# wifi_watering_system_1.net
KiCad netlist of a schematic drawn in Altium Designer
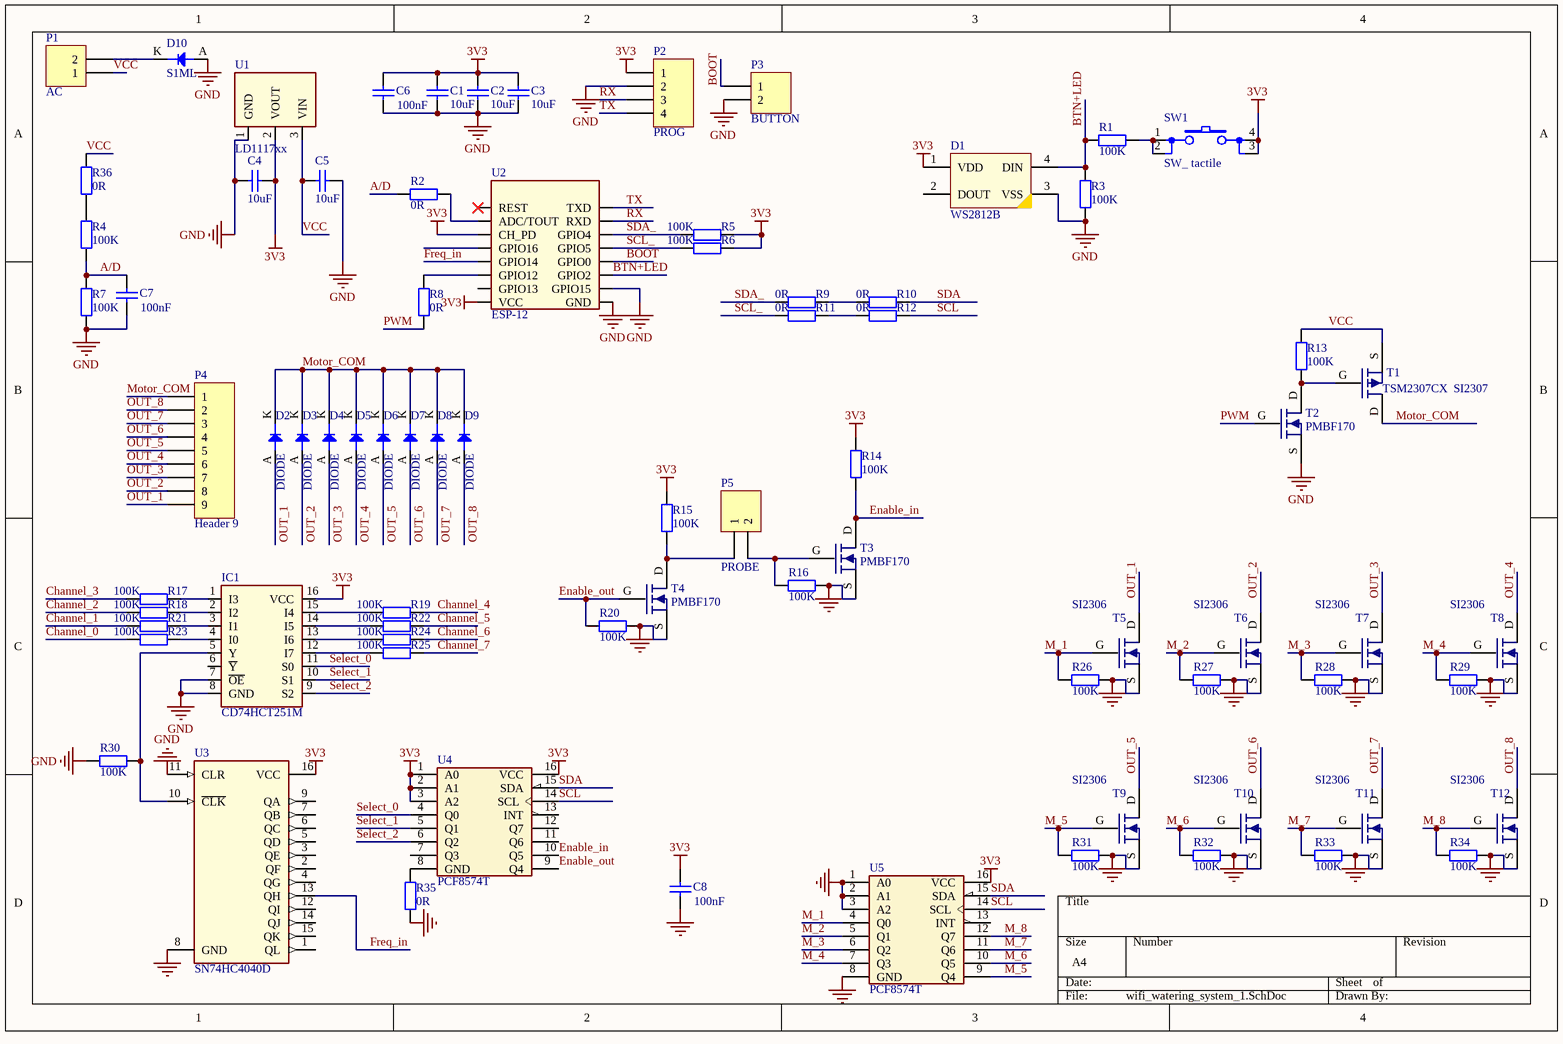
[diagram p0: wifi_watering_system_1.SchDoc]

(export (version "E")
  (design (tool "Eeschema 10.0.6"))
  (components
    (comp (ref "C1")
      (value "10uF")
      (footprint "FP_1206_CAP_085")
      (description "Capacitor")
      (fields (field (name "PUBLISHER") "Altium Limited"))
      (libsource (lib "Miscellaneous Devices") (part "Cap"))
    )
    (comp (ref "C2")
      (value "10uF")
      (footprint "FP_1206_CAP_085")
      (description "Capacitor")
      (fields (field (name "PUBLISHER") "Altium Limited"))
      (libsource (lib "Miscellaneous Devices") (part "Cap"))
    )
    (comp (ref "C3")
      (value "10uF")
      (footprint "FP_1206_CAP_085")
      (description "Capacitor")
      (fields (field (name "PUBLISHER") "Altium Limited"))
      (libsource (lib "Miscellaneous Devices") (part "Cap"))
    )
    (comp (ref "C4")
      (value "10uF")
      (footprint "FP_1206_CAP_085")
      (description "Capacitor")
      (fields (field (name "PUBLISHER") "Altium Limited"))
      (libsource (lib "Miscellaneous Devices") (part "Cap"))
    )
    (comp (ref "C5")
      (value "10uF")
      (footprint "FP_1206_CAP_085")
      (description "Capacitor")
      (fields (field (name "PUBLISHER") "Altium Limited"))
      (libsource (lib "Miscellaneous Devices") (part "Cap"))
    )
    (comp (ref "C6")
      (value "100nF")
      (footprint "FP_0603_CAP_080")
      (description "Capacitor")
      (libsource (lib "Miscellaneous Devices") (part "Cap"))
    )
    (comp (ref "C7")
      (value "100nF")
      (footprint "FP_0603_CAP_080")
      (description "Capacitor")
      (libsource (lib "Miscellaneous Devices") (part "Cap"))
    )
    (comp (ref "C8")
      (value "100nF")
      (footprint "FP_0603_CAP_080")
      (description "Capacitor")
      (libsource (lib "Miscellaneous Devices") (part "Cap"))
    )
    (comp (ref "D1")
      (value "WS2812B")
      (footprint "LED_5050_4pin")
      (libsource (lib "Led_optical") (part "WS2812B"))
    )
    (comp (ref "D2")
      (value "DIODE")
      (footprint "SOD-80")
      (description "Diode")
      (libsource (lib "Diode") (part "DIODE"))
    )
    (comp (ref "D3")
      (value "DIODE")
      (footprint "SOD-80")
      (description "Diode")
      (libsource (lib "Diode") (part "DIODE"))
    )
    (comp (ref "D4")
      (value "DIODE")
      (footprint "SOD-80")
      (description "Diode")
      (libsource (lib "Diode") (part "DIODE"))
    )
    (comp (ref "D5")
      (value "DIODE")
      (footprint "SOD-80")
      (description "Diode")
      (libsource (lib "Diode") (part "DIODE"))
    )
    (comp (ref "D6")
      (value "DIODE")
      (footprint "SOD-80")
      (description "Diode")
      (libsource (lib "Diode") (part "DIODE"))
    )
    (comp (ref "D7")
      (value "DIODE")
      (footprint "SOD-80")
      (description "Diode")
      (libsource (lib "Diode") (part "DIODE"))
    )
    (comp (ref "D8")
      (value "DIODE")
      (footprint "SOD-80")
      (description "Diode")
      (libsource (lib "Diode") (part "DIODE"))
    )
    (comp (ref "D9")
      (value "DIODE")
      (footprint "SOD-80")
      (description "Diode")
      (libsource (lib "Diode") (part "DIODE"))
    )
    (comp (ref "D10")
      (value "S1ML")
      (footprint "subsma")
      (description "Diode")
      (libsource (lib "Diode") (part "DIODE"))
    )
    (comp (ref "IC1")
      (value "CD74HCT251M")
      (footprint "GATE_SOIC16")
      (description "CD74HCT251M 8-INPUT MUX.WITH 3-STATE OUTP")
      (libsource (lib "Logic_gate") (part "CD74HCT251M"))
    )
    (comp (ref "P1")
      (value "AC")
      (footprint "Sorkapocs 2P 5mm")
      (description "Header, 2-Pin")
      (fields (field (name "PUBLISHER") "Altium Limited"))
      (libsource (lib "Miscellaneous Connectors") (part "Header 2"))
    )
    (comp (ref "P2")
      (value "PROG")
      (footprint "HDR1X4")
      (description "Header, 4-Pin")
      (fields (field (name "PUBLISHER") "Altium Limited"))
      (libsource (lib "Miscellaneous Connectors") (part "Header 4"))
    )
    (comp (ref "P3")
      (value "BUTTON")
      (footprint "HDR1X2")
      (description "Header, 2-Pin")
      (fields (field (name "PUBLISHER") "Altium Limited"))
      (libsource (lib "") (part "Header 2_1"))
    )
    (comp (ref "P4")
      (value "Header 9")
      (footprint "Sorkapocs 9P 5mm")
      (description "Header, 9-Pin")
      (fields (field (name "PUBLISHER") "Altium Limited"))
      (libsource (lib "Miscellaneous Connectors") (part "Header 9"))
    )
    (comp (ref "P5")
      (value "PROBE")
      (footprint "HDR1X2")
      (description "Header, 2-Pin")
      (fields (field (name "PUBLISHER") "Altium Limited"))
      (libsource (lib "") (part "Header 2_2"))
    )
    (comp (ref "R1")
      (value "100K")
      (footprint "FP_0603_RES")
      (description "Resistor")
      (libsource (lib "Resistor") (part "RES"))
    )
    (comp (ref "R2")
      (value "0R")
      (footprint "FP_1206_RES")
      (description "Resistor")
      (libsource (lib "") (part "RES_3"))
    )
    (comp (ref "R3")
      (value "100K")
      (footprint "FP_0603_RES")
      (description "Resistor")
      (libsource (lib "") (part "RES_2"))
    )
    (comp (ref "R4")
      (value "100K")
      (footprint "FP_0603_RES")
      (description "Resistor")
      (libsource (lib "") (part "RES_2"))
    )
    (comp (ref "R5")
      (value "100K")
      (footprint "FP_0603_RES")
      (description "Resistor")
      (libsource (lib "") (part "RES_3"))
    )
    (comp (ref "R6")
      (value "100K")
      (footprint "FP_0603_RES")
      (description "Resistor")
      (libsource (lib "") (part "RES_3"))
    )
    (comp (ref "R7")
      (value "100K")
      (footprint "FP_0603_RES")
      (description "Resistor")
      (libsource (lib "") (part "RES_2"))
    )
    (comp (ref "R8")
      (value "0R")
      (footprint "FP_1206_RES")
      (description "Resistor")
      (libsource (lib "") (part "RES_2"))
    )
    (comp (ref "R9")
      (value "0R")
      (footprint "FP_1206_RES")
      (description "Resistor")
      (libsource (lib "") (part "RES_3"))
    )
    (comp (ref "R10")
      (value "0R")
      (footprint "FP_1206_RES")
      (description "Resistor")
      (libsource (lib "") (part "RES_3"))
    )
    (comp (ref "R11")
      (value "0R")
      (footprint "FP_1206_RES")
      (description "Resistor")
      (libsource (lib "") (part "RES_3"))
    )
    (comp (ref "R12")
      (value "0R")
      (footprint "FP_1206_RES")
      (description "Resistor")
      (libsource (lib "") (part "RES_3"))
    )
    (comp (ref "R13")
      (value "100K")
      (footprint "FP_0603_RES")
      (description "Resistor")
      (libsource (lib "") (part "RES_2"))
    )
    (comp (ref "R14")
      (value "100K")
      (footprint "FP_0603_RES")
      (description "Resistor")
      (libsource (lib "") (part "RES_1"))
    )
    (comp (ref "R15")
      (value "100K")
      (footprint "FP_0603_RES")
      (description "Resistor")
      (libsource (lib "") (part "RES_1"))
    )
    (comp (ref "R16")
      (value "100K")
      (footprint "FP_0603_RES")
      (description "Resistor")
      (libsource (lib "") (part "RES_3"))
    )
    (comp (ref "R17")
      (value "100K")
      (footprint "FP_0603_RES")
      (description "Resistor")
      (libsource (lib "Resistor") (part "RES"))
    )
    (comp (ref "R18")
      (value "100K")
      (footprint "FP_0603_RES")
      (description "Resistor")
      (libsource (lib "Resistor") (part "RES"))
    )
    (comp (ref "R19")
      (value "100K")
      (footprint "FP_0603_RES")
      (description "Resistor")
      (libsource (lib "Resistor") (part "RES"))
    )
    (comp (ref "R20")
      (value "100K")
      (footprint "FP_0603_RES")
      (description "Resistor")
      (libsource (lib "") (part "RES_3"))
    )
    (comp (ref "R21")
      (value "100K")
      (footprint "FP_0603_RES")
      (description "Resistor")
      (libsource (lib "Resistor") (part "RES"))
    )
    (comp (ref "R22")
      (value "100K")
      (footprint "FP_0603_RES")
      (description "Resistor")
      (libsource (lib "Resistor") (part "RES"))
    )
    (comp (ref "R23")
      (value "100K")
      (footprint "FP_0603_RES")
      (description "Resistor")
      (libsource (lib "Resistor") (part "RES"))
    )
    (comp (ref "R24")
      (value "100K")
      (footprint "FP_0603_RES")
      (description "Resistor")
      (libsource (lib "Resistor") (part "RES"))
    )
    (comp (ref "R25")
      (value "100K")
      (footprint "FP_0603_RES")
      (description "Resistor")
      (libsource (lib "Resistor") (part "RES"))
    )
    (comp (ref "R26")
      (value "100K")
      (footprint "FP_0603_RES")
      (description "Resistor")
      (libsource (lib "Resistor") (part "RES"))
    )
    (comp (ref "R27")
      (value "100K")
      (footprint "FP_0603_RES")
      (description "Resistor")
      (libsource (lib "") (part "RES_3"))
    )
    (comp (ref "R28")
      (value "100K")
      (footprint "FP_0603_RES")
      (description "Resistor")
      (libsource (lib "") (part "RES_3"))
    )
    (comp (ref "R29")
      (value "100K")
      (footprint "FP_0603_RES")
      (description "Resistor")
      (libsource (lib "") (part "RES_3"))
    )
    (comp (ref "R30")
      (value "100K")
      (footprint "FP_0603_RES")
      (description "Resistor")
      (libsource (lib "Resistor") (part "RES"))
    )
    (comp (ref "R31")
      (value "100K")
      (footprint "FP_0603_RES")
      (description "Resistor")
      (libsource (lib "") (part "RES_3"))
    )
    (comp (ref "R32")
      (value "100K")
      (footprint "FP_0603_RES")
      (description "Resistor")
      (libsource (lib "") (part "RES_3"))
    )
    (comp (ref "R33")
      (value "100K")
      (footprint "FP_0603_RES")
      (description "Resistor")
      (libsource (lib "") (part "RES_3"))
    )
    (comp (ref "R34")
      (value "100K")
      (footprint "FP_0603_RES")
      (description "Resistor")
      (libsource (lib "") (part "RES_3"))
    )
    (comp (ref "R35")
      (value "0R")
      (footprint "FP_1206_RES")
      (description "Resistor")
      (libsource (lib "") (part "RES_2"))
    )
    (comp (ref "R36")
      (value "0R")
      (footprint "FP_1206_RES")
      (description "Resistor")
      (libsource (lib "") (part "RES_2"))
    )
    (comp (ref "SW1")
      (value "SW_ tactile")
      (footprint "FP_TACTBTN")
      (libsource (lib "Switch") (part "SW_ tactile"))
    )
    (comp (ref "T1")
      (value "TSM2307CX  SI2307")
      (footprint "FET_SOT23")
      (libsource (lib "FET") (part "PMOS"))
    )
    (comp (ref "T2") (value "PMBF170") (footprint "FET_SOT23") (libsource (lib "FET") (part "NMOS")))
    (comp (ref "T3") (value "PMBF170") (footprint "FET_SOT23") (libsource (lib "FET") (part "NMOS")))
    (comp (ref "T4") (value "PMBF170") (footprint "FET_SOT23") (libsource (lib "FET") (part "NMOS")))
    (comp (ref "T5") (value "SI2306") (footprint "FET_SOT23") (libsource (lib "FET") (part "NMOS")))
    (comp (ref "T6") (value "SI2306") (footprint "FET_SOT23") (libsource (lib "FET") (part "NMOS")))
    (comp (ref "T7") (value "SI2306") (footprint "FET_SOT23") (libsource (lib "FET") (part "NMOS")))
    (comp (ref "T8") (value "SI2306") (footprint "FET_SOT23") (libsource (lib "FET") (part "NMOS")))
    (comp (ref "T9") (value "SI2306") (footprint "FET_SOT23") (libsource (lib "FET") (part "NMOS")))
    (comp (ref "T10") (value "SI2306") (footprint "FET_SOT23") (libsource (lib "FET") (part "NMOS")))
    (comp (ref "T11") (value "SI2306") (footprint "FET_SOT23") (libsource (lib "FET") (part "NMOS")))
    (comp (ref "T12") (value "SI2306") (footprint "FET_SOT23") (libsource (lib "FET") (part "NMOS")))
    (comp (ref "U1")
      (value "LD1117xx")
      (footprint "SUPPLY_SOT223")
      (description "LD1117xx 3,3V lin reg")
      (libsource (lib "Supply") (part "LD1117xx"))
    )
    (comp (ref "U2")
      (value "ESP-12")
      (footprint "ESP_12")
      (description "ESP-12 wifi module")
      (libsource (lib "Modul") (part "ESP-12"))
    )
    (comp (ref "U3")
      (value "SN74HC4040D")
      (footprint "GATE_SOIC16")
      (description "12-Bit Asynchronous Binary Counter")
      (libsource (lib "Logic_gate") (part "SN74HC4040D"))
    )
    (comp (ref "U4")
      (value "PCF8574T")
      (footprint "DIGITAL_SOIC16W")
      (libsource (lib "Digital") (part "PCF8574T"))
    )
    (comp (ref "U5")
      (value "PCF8574T")
      (footprint "DIGITAL_SOIC16W")
      (libsource (lib "Digital") (part "PCF8574T"))
    )
  )
  (nets
    (net (code "1") (name "/A{slash}D") (class "Default")
      (node (ref "C7") (pin "1") (pinfunction "1_1") (pintype "passive"))
      (node (ref "R2") (pin "2") (pinfunction "2_2") (pintype "passive"))
      (node (ref "R4") (pin "2") (pinfunction "2_2") (pintype "passive"))
      (node (ref "R7") (pin "1") (pinfunction "1_1") (pintype "passive"))
    )
    (net (code "2") (name "/BOOT") (class "Default")
      (node (ref "P3") (pin "1") (pinfunction "1_1") (pintype "passive"))
      (node (ref "U2") (pin "12") (pinfunction "GPIO0_12") (pintype "passive"))
    )
    (net (code "3") (name "/BTN+LED") (class "Default")
      (node (ref "D1") (pin "4") (pinfunction "DIN_4") (pintype "passive"))
      (node (ref "R1") (pin "1") (pinfunction "1_1") (pintype "passive"))
      (node (ref "R3") (pin "1") (pinfunction "1_1") (pintype "passive"))
      (node (ref "U2") (pin "11") (pinfunction "GPIO2_11") (pintype "passive"))
    )
    (net (code "4") (name "/Channel_0") (class "Default")
      (node (ref "R23") (pin "1") (pinfunction "1_1") (pintype "passive"))
    )
    (net (code "5") (name "/Channel_1") (class "Default")
      (node (ref "R21") (pin "1") (pinfunction "1_1") (pintype "passive"))
    )
    (net (code "6") (name "/Channel_2") (class "Default")
      (node (ref "R18") (pin "1") (pinfunction "1_1") (pintype "passive"))
    )
    (net (code "7") (name "/Channel_3") (class "Default")
      (node (ref "R17") (pin "1") (pinfunction "1_1") (pintype "passive"))
    )
    (net (code "8") (name "/Channel_4") (class "Default")
      (node (ref "R19") (pin "2") (pinfunction "2_2") (pintype "passive"))
    )
    (net (code "9") (name "/Channel_5") (class "Default")
      (node (ref "R22") (pin "2") (pinfunction "2_2") (pintype "passive"))
    )
    (net (code "10") (name "/Channel_6") (class "Default")
      (node (ref "R24") (pin "2") (pinfunction "2_2") (pintype "passive"))
    )
    (net (code "11") (name "/Channel_7") (class "Default")
      (node (ref "R25") (pin "2") (pinfunction "2_2") (pintype "passive"))
    )
    (net (code "12") (name "/Enable_in") (class "Default")
      (node (ref "R14") (pin "1") (pinfunction "1_1") (pintype "passive"))
      (node (ref "T3") (pin "D") (pinfunction "D_D") (pintype "passive"))
      (node (ref "U4") (pin "10") (pinfunction "Q5_10") (pintype "passive"))
    )
    (net (code "13") (name "/Enable_out") (class "Default")
      (node (ref "R20") (pin "2") (pinfunction "2_2") (pintype "passive"))
      (node (ref "T4") (pin "G") (pinfunction "G_G") (pintype "passive"))
      (node (ref "U4") (pin "9") (pinfunction "Q4_9") (pintype "passive"))
    )
    (net (code "14") (name "/Freq_in") (class "Default")
      (node (ref "U2") (pin "5") (pinfunction "GPIO14_5") (pintype "passive"))
      (node (ref "U3") (pin "13") (pinfunction "QH_13") (pintype "output"))
    )
    (net (code "15") (name "/M_1") (class "Default")
      (node (ref "R26") (pin "1") (pinfunction "1_1") (pintype "passive"))
      (node (ref "T5") (pin "G") (pinfunction "G_G") (pintype "passive"))
      (node (ref "U5") (pin "4") (pinfunction "Q0_4") (pintype "passive"))
    )
    (net (code "16") (name "/M_2") (class "Default")
      (node (ref "R27") (pin "2") (pinfunction "2_2") (pintype "passive"))
      (node (ref "T6") (pin "G") (pinfunction "G_G") (pintype "passive"))
      (node (ref "U5") (pin "5") (pinfunction "Q1_5") (pintype "passive"))
    )
    (net (code "17") (name "/M_3") (class "Default")
      (node (ref "R28") (pin "2") (pinfunction "2_2") (pintype "passive"))
      (node (ref "T7") (pin "G") (pinfunction "G_G") (pintype "passive"))
      (node (ref "U5") (pin "6") (pinfunction "Q2_6") (pintype "passive"))
    )
    (net (code "18") (name "/M_4") (class "Default")
      (node (ref "R29") (pin "2") (pinfunction "2_2") (pintype "passive"))
      (node (ref "T8") (pin "G") (pinfunction "G_G") (pintype "passive"))
      (node (ref "U5") (pin "7") (pinfunction "Q3_7") (pintype "passive"))
    )
    (net (code "19") (name "/M_5") (class "Default")
      (node (ref "R31") (pin "2") (pinfunction "2_2") (pintype "passive"))
      (node (ref "T9") (pin "G") (pinfunction "G_G") (pintype "passive"))
      (node (ref "U5") (pin "9") (pinfunction "Q4_9") (pintype "passive"))
    )
    (net (code "20") (name "/M_6") (class "Default")
      (node (ref "R32") (pin "2") (pinfunction "2_2") (pintype "passive"))
      (node (ref "T10") (pin "G") (pinfunction "G_G") (pintype "passive"))
      (node (ref "U5") (pin "10") (pinfunction "Q5_10") (pintype "passive"))
    )
    (net (code "21") (name "/M_7") (class "Default")
      (node (ref "R33") (pin "2") (pinfunction "2_2") (pintype "passive"))
      (node (ref "T11") (pin "G") (pinfunction "G_G") (pintype "passive"))
      (node (ref "U5") (pin "11") (pinfunction "Q6_11") (pintype "passive"))
    )
    (net (code "22") (name "/M_8") (class "Default")
      (node (ref "R34") (pin "2") (pinfunction "2_2") (pintype "passive"))
      (node (ref "T12") (pin "G") (pinfunction "G_G") (pintype "passive"))
      (node (ref "U5") (pin "12") (pinfunction "Q7_12") (pintype "passive"))
    )
    (net (code "23") (name "/Motor_COM") (class "Default")
      (node (ref "D2") (pin "K") (pinfunction "K_K") (pintype "passive"))
      (node (ref "D3") (pin "K") (pinfunction "K_K") (pintype "passive"))
      (node (ref "D4") (pin "K") (pinfunction "K_K") (pintype "passive"))
      (node (ref "D5") (pin "K") (pinfunction "K_K") (pintype "passive"))
      (node (ref "D6") (pin "K") (pinfunction "K_K") (pintype "passive"))
      (node (ref "D7") (pin "K") (pinfunction "K_K") (pintype "passive"))
      (node (ref "D8") (pin "K") (pinfunction "K_K") (pintype "passive"))
      (node (ref "D9") (pin "K") (pinfunction "K_K") (pintype "passive"))
      (node (ref "P4") (pin "1") (pinfunction "1_1") (pintype "passive"))
      (node (ref "T1") (pin "D") (pinfunction "D_D") (pintype "passive"))
    )
    (net (code "24") (name "/OUT_1") (class "Default")
      (node (ref "D2") (pin "A") (pinfunction "A_A") (pintype "passive"))
      (node (ref "P4") (pin "9") (pinfunction "9_9") (pintype "passive"))
      (node (ref "T5") (pin "D") (pinfunction "D_D") (pintype "passive"))
    )
    (net (code "25") (name "/OUT_2") (class "Default")
      (node (ref "D3") (pin "A") (pinfunction "A_A") (pintype "passive"))
      (node (ref "P4") (pin "8") (pinfunction "8_8") (pintype "passive"))
      (node (ref "T6") (pin "D") (pinfunction "D_D") (pintype "passive"))
    )
    (net (code "26") (name "/OUT_3") (class "Default")
      (node (ref "D4") (pin "A") (pinfunction "A_A") (pintype "passive"))
      (node (ref "P4") (pin "7") (pinfunction "7_7") (pintype "passive"))
      (node (ref "T7") (pin "D") (pinfunction "D_D") (pintype "passive"))
    )
    (net (code "27") (name "/OUT_4") (class "Default")
      (node (ref "D5") (pin "A") (pinfunction "A_A") (pintype "passive"))
      (node (ref "P4") (pin "6") (pinfunction "6_6") (pintype "passive"))
      (node (ref "T8") (pin "D") (pinfunction "D_D") (pintype "passive"))
    )
    (net (code "28") (name "/OUT_5") (class "Default")
      (node (ref "D6") (pin "A") (pinfunction "A_A") (pintype "passive"))
      (node (ref "P4") (pin "5") (pinfunction "5_5") (pintype "passive"))
      (node (ref "T9") (pin "D") (pinfunction "D_D") (pintype "passive"))
    )
    (net (code "29") (name "/OUT_6") (class "Default")
      (node (ref "D7") (pin "A") (pinfunction "A_A") (pintype "passive"))
      (node (ref "P4") (pin "4") (pinfunction "4_4") (pintype "passive"))
      (node (ref "T10") (pin "D") (pinfunction "D_D") (pintype "passive"))
    )
    (net (code "30") (name "/OUT_7") (class "Default")
      (node (ref "D8") (pin "A") (pinfunction "A_A") (pintype "passive"))
      (node (ref "P4") (pin "3") (pinfunction "3_3") (pintype "passive"))
      (node (ref "T11") (pin "D") (pinfunction "D_D") (pintype "passive"))
    )
    (net (code "31") (name "/OUT_8") (class "Default")
      (node (ref "D9") (pin "A") (pinfunction "A_A") (pintype "passive"))
      (node (ref "P4") (pin "2") (pinfunction "2_2") (pintype "passive"))
      (node (ref "T12") (pin "D") (pinfunction "D_D") (pintype "passive"))
    )
    (net (code "32") (name "/PWM") (class "Default")
      (node (ref "R8") (pin "2") (pinfunction "2_2") (pintype "passive"))
      (node (ref "T2") (pin "G") (pinfunction "G_G") (pintype "passive"))
    )
    (net (code "33") (name "/RX") (class "Default")
      (node (ref "P2") (pin "3") (pinfunction "3_3") (pintype "passive"))
      (node (ref "U2") (pin "15") (pinfunction "RXD_15") (pintype "passive"))
    )
    (net (code "34") (name "/SCL") (class "Default")
      (node (ref "R12") (pin "1") (pinfunction "1_1") (pintype "passive"))
      (node (ref "U4") (pin "14") (pinfunction "SCL_14") (pintype "passive"))
      (node (ref "U5") (pin "14") (pinfunction "SCL_14") (pintype "passive"))
    )
    (net (code "35") (name "/SCL_") (class "Default")
      (node (ref "R11") (pin "2") (pinfunction "2_2") (pintype "passive"))
      (node (ref "R6") (pin "2") (pinfunction "2_2") (pintype "passive"))
      (node (ref "U2") (pin "13") (pinfunction "GPIO5_13") (pintype "passive"))
    )
    (net (code "36") (name "/SDA") (class "Default")
      (node (ref "R10") (pin "1") (pinfunction "1_1") (pintype "passive"))
      (node (ref "U4") (pin "15") (pinfunction "SDA_15") (pintype "passive"))
      (node (ref "U5") (pin "15") (pinfunction "SDA_15") (pintype "passive"))
    )
    (net (code "37") (name "/SDA_") (class "Default")
      (node (ref "R5") (pin "2") (pinfunction "2_2") (pintype "passive"))
      (node (ref "R9") (pin "2") (pinfunction "2_2") (pintype "passive"))
      (node (ref "U2") (pin "14") (pinfunction "GPIO4_14") (pintype "passive"))
    )
    (net (code "38") (name "/Select_0") (class "Default")
      (node (ref "IC1") (pin "11") (pinfunction "S0_11") (pintype "passive"))
      (node (ref "U4") (pin "4") (pinfunction "Q0_4") (pintype "passive"))
    )
    (net (code "39") (name "/Select_1") (class "Default")
      (node (ref "IC1") (pin "10") (pinfunction "S1_10") (pintype "passive"))
      (node (ref "U4") (pin "5") (pinfunction "Q1_5") (pintype "passive"))
    )
    (net (code "40") (name "/Select_2") (class "Default")
      (node (ref "IC1") (pin "9") (pinfunction "S2_9") (pintype "passive"))
      (node (ref "U4") (pin "6") (pinfunction "Q2_6") (pintype "passive"))
    )
    (net (code "41") (name "/TX") (class "Default")
      (node (ref "P2") (pin "4") (pinfunction "4_4") (pintype "passive"))
      (node (ref "U2") (pin "16") (pinfunction "TXD_16") (pintype "passive"))
    )
    (net (code "42") (name "/VCC") (class "Default")
      (node (ref "C5") (pin "1") (pinfunction "1_1") (pintype "passive"))
      (node (ref "P1") (pin "1") (pinfunction "1_1") (pintype "passive"))
      (node (ref "R13") (pin "1") (pinfunction "1_1") (pintype "passive"))
      (node (ref "R36") (pin "1") (pinfunction "1_1") (pintype "passive"))
      (node (ref "T1") (pin "S") (pinfunction "S_S") (pintype "passive"))
      (node (ref "U1") (pin "3") (pinfunction "VIN_3") (pintype "passive"))
    )
    (net (code "43") (name "3V3") (class "Default")
      (node (ref "C1") (pin "2") (pinfunction "2_2") (pintype "passive"))
      (node (ref "C2") (pin "2") (pinfunction "2_2") (pintype "passive"))
      (node (ref "C3") (pin "2") (pinfunction "2_2") (pintype "passive"))
      (node (ref "C4") (pin "2") (pinfunction "2_2") (pintype "passive"))
      (node (ref "C6") (pin "1") (pinfunction "1_1") (pintype "passive"))
      (node (ref "C8") (pin "1") (pinfunction "1_1") (pintype "passive"))
      (node (ref "D1") (pin "1") (pinfunction "VDD_1") (pintype "passive"))
      (node (ref "IC1") (pin "16") (pinfunction "VCC_16") (pintype "passive"))
      (node (ref "P2") (pin "1") (pinfunction "1_1") (pintype "passive"))
      (node (ref "R14") (pin "2") (pinfunction "2_2") (pintype "passive"))
      (node (ref "R15") (pin "2") (pinfunction "2_2") (pintype "passive"))
      (node (ref "R5") (pin "1") (pinfunction "1_1") (pintype "passive"))
      (node (ref "R6") (pin "1") (pinfunction "1_1") (pintype "passive"))
      (node (ref "SW1") (pin "3") (pinfunction "3_3") (pintype "passive"))
      (node (ref "SW1") (pin "4") (pinfunction "4_4") (pintype "passive"))
      (node (ref "U1") (pin "2") (pinfunction "VOUT_2") (pintype "passive"))
      (node (ref "U2") (pin "3") (pinfunction "CH_PD_3") (pintype "passive"))
      (node (ref "U2") (pin "8") (pinfunction "VCC_8") (pintype "passive"))
      (node (ref "U3") (pin "16") (pinfunction "VCC_16") (pintype "passive"))
      (node (ref "U4") (pin "1") (pinfunction "A0_1") (pintype "passive"))
      (node (ref "U4") (pin "16") (pinfunction "VCC_16") (pintype "passive"))
      (node (ref "U4") (pin "2") (pinfunction "A1_2") (pintype "passive"))
      (node (ref "U4") (pin "3") (pinfunction "A2_3") (pintype "passive"))
      (node (ref "U5") (pin "16") (pinfunction "VCC_16") (pintype "passive"))
    )
    (net (code "44") (name "GND") (class "Default")
      (node (ref "C1") (pin "1") (pinfunction "1_1") (pintype "passive"))
      (node (ref "C2") (pin "1") (pinfunction "1_1") (pintype "passive"))
      (node (ref "C3") (pin "1") (pinfunction "1_1") (pintype "passive"))
      (node (ref "C4") (pin "1") (pinfunction "1_1") (pintype "passive"))
      (node (ref "C5") (pin "2") (pinfunction "2_2") (pintype "passive"))
      (node (ref "C6") (pin "2") (pinfunction "2_2") (pintype "passive"))
      (node (ref "C7") (pin "2") (pinfunction "2_2") (pintype "passive"))
      (node (ref "C8") (pin "2") (pinfunction "2_2") (pintype "passive"))
      (node (ref "D1") (pin "3") (pinfunction "VSS_3") (pintype "passive"))
      (node (ref "D10") (pin "A") (pinfunction "A_A") (pintype "passive"))
      (node (ref "IC1") (pin "7") (pinfunction "~{OE}_7") (pintype "passive"))
      (node (ref "IC1") (pin "8") (pinfunction "GND_8") (pintype "passive"))
      (node (ref "P2") (pin "2") (pinfunction "2_2") (pintype "passive"))
      (node (ref "P3") (pin "2") (pinfunction "2_2") (pintype "passive"))
      (node (ref "R16") (pin "1") (pinfunction "1_1") (pintype "passive"))
      (node (ref "R20") (pin "1") (pinfunction "1_1") (pintype "passive"))
      (node (ref "R26") (pin "2") (pinfunction "2_2") (pintype "passive"))
      (node (ref "R27") (pin "1") (pinfunction "1_1") (pintype "passive"))
      (node (ref "R28") (pin "1") (pinfunction "1_1") (pintype "passive"))
      (node (ref "R29") (pin "1") (pinfunction "1_1") (pintype "passive"))
      (node (ref "R3") (pin "2") (pinfunction "2_2") (pintype "passive"))
      (node (ref "R30") (pin "1") (pinfunction "1_1") (pintype "passive"))
      (node (ref "R31") (pin "1") (pinfunction "1_1") (pintype "passive"))
      (node (ref "R32") (pin "1") (pinfunction "1_1") (pintype "passive"))
      (node (ref "R33") (pin "1") (pinfunction "1_1") (pintype "passive"))
      (node (ref "R34") (pin "1") (pinfunction "1_1") (pintype "passive"))
      (node (ref "R35") (pin "2") (pinfunction "2_2") (pintype "passive"))
      (node (ref "R7") (pin "2") (pinfunction "2_2") (pintype "passive"))
      (node (ref "T10") (pin "S") (pinfunction "S_S") (pintype "passive"))
      (node (ref "T11") (pin "S") (pinfunction "S_S") (pintype "passive"))
      (node (ref "T12") (pin "S") (pinfunction "S_S") (pintype "passive"))
      (node (ref "T2") (pin "S") (pinfunction "S_S") (pintype "passive"))
      (node (ref "T3") (pin "S") (pinfunction "S_S") (pintype "passive"))
      (node (ref "T4") (pin "S") (pinfunction "S_S") (pintype "passive"))
      (node (ref "T5") (pin "S") (pinfunction "S_S") (pintype "passive"))
      (node (ref "T6") (pin "S") (pinfunction "S_S") (pintype "passive"))
      (node (ref "T7") (pin "S") (pinfunction "S_S") (pintype "passive"))
      (node (ref "T8") (pin "S") (pinfunction "S_S") (pintype "passive"))
      (node (ref "T9") (pin "S") (pinfunction "S_S") (pintype "passive"))
      (node (ref "U1") (pin "1") (pinfunction "GND_1") (pintype "passive"))
      (node (ref "U2") (pin "10") (pinfunction "GPIO15_10") (pintype "passive"))
      (node (ref "U2") (pin "9") (pinfunction "GND_9") (pintype "passive"))
      (node (ref "U3") (pin "11") (pinfunction "CLR_11") (pintype "input"))
      (node (ref "U3") (pin "8") (pinfunction "GND_8") (pintype "passive"))
      (node (ref "U5") (pin "1") (pinfunction "A0_1") (pintype "passive"))
      (node (ref "U5") (pin "2") (pinfunction "A1_2") (pintype "passive"))
      (node (ref "U5") (pin "3") (pinfunction "A2_3") (pintype "passive"))
      (node (ref "U5") (pin "8") (pinfunction "GND_8") (pintype "passive"))
    )
    (net (code "45") (name "Net-(D10-PadK)") (class "Default")
      (node (ref "D10") (pin "K") (pinfunction "K_K") (pintype "passive"))
      (node (ref "P1") (pin "2") (pinfunction "2_2") (pintype "passive"))
    )
    (net (code "46") (name "Net-(IC1-I0)") (class "Default")
      (node (ref "IC1") (pin "4") (pinfunction "I0_4") (pintype "passive"))
      (node (ref "R23") (pin "2") (pinfunction "2_2") (pintype "passive"))
    )
    (net (code "47") (name "Net-(IC1-I1)") (class "Default")
      (node (ref "IC1") (pin "3") (pinfunction "I1_3") (pintype "passive"))
      (node (ref "R21") (pin "2") (pinfunction "2_2") (pintype "passive"))
    )
    (net (code "48") (name "Net-(IC1-I2)") (class "Default")
      (node (ref "IC1") (pin "2") (pinfunction "I2_2") (pintype "passive"))
      (node (ref "R18") (pin "2") (pinfunction "2_2") (pintype "passive"))
    )
    (net (code "49") (name "Net-(IC1-I3)") (class "Default")
      (node (ref "IC1") (pin "1") (pinfunction "I3_1") (pintype "passive"))
      (node (ref "R17") (pin "2") (pinfunction "2_2") (pintype "passive"))
    )
    (net (code "50") (name "Net-(IC1-I4)") (class "Default")
      (node (ref "IC1") (pin "15") (pinfunction "I4_15") (pintype "passive"))
      (node (ref "R19") (pin "1") (pinfunction "1_1") (pintype "passive"))
    )
    (net (code "51") (name "Net-(IC1-I5)") (class "Default")
      (node (ref "IC1") (pin "14") (pinfunction "I5_14") (pintype "passive"))
      (node (ref "R22") (pin "1") (pinfunction "1_1") (pintype "passive"))
    )
    (net (code "52") (name "Net-(IC1-I6)") (class "Default")
      (node (ref "IC1") (pin "13") (pinfunction "I6_13") (pintype "passive"))
      (node (ref "R24") (pin "1") (pinfunction "1_1") (pintype "passive"))
    )
    (net (code "53") (name "Net-(IC1-I7)") (class "Default")
      (node (ref "IC1") (pin "12") (pinfunction "I7_12") (pintype "passive"))
      (node (ref "R25") (pin "1") (pinfunction "1_1") (pintype "passive"))
    )
    (net (code "54") (name "Net-(IC1-Y)") (class "Default")
      (node (ref "IC1") (pin "5") (pinfunction "Y_5") (pintype "passive"))
      (node (ref "R30") (pin "2") (pinfunction "2_2") (pintype "passive"))
      (node (ref "U3") (pin "10") (pinfunction "~{CLK}_10") (pintype "input"))
    )
    (net (code "55") (name "Net-(P5-Pad1)") (class "Default")
      (node (ref "P5") (pin "1") (pinfunction "1_1") (pintype "passive"))
      (node (ref "R15") (pin "1") (pinfunction "1_1") (pintype "passive"))
      (node (ref "T4") (pin "D") (pinfunction "D_D") (pintype "passive"))
    )
    (net (code "56") (name "Net-(P5-Pad2)") (class "Default")
      (node (ref "P5") (pin "2") (pinfunction "2_2") (pintype "passive"))
      (node (ref "R16") (pin "2") (pinfunction "2_2") (pintype "passive"))
      (node (ref "T3") (pin "G") (pinfunction "G_G") (pintype "passive"))
    )
    (net (code "57") (name "Net-(R1-Pad2)") (class "Default")
      (node (ref "R1") (pin "2") (pinfunction "2_2") (pintype "passive"))
      (node (ref "SW1") (pin "1") (pinfunction "1_1") (pintype "passive"))
      (node (ref "SW1") (pin "2") (pinfunction "2_2") (pintype "passive"))
    )
    (net (code "58") (name "Net-(R10-Pad2)") (class "Default")
      (node (ref "R10") (pin "2") (pinfunction "2_2") (pintype "passive"))
      (node (ref "R9") (pin "1") (pinfunction "1_1") (pintype "passive"))
    )
    (net (code "59") (name "Net-(R11-Pad1)") (class "Default")
      (node (ref "R11") (pin "1") (pinfunction "1_1") (pintype "passive"))
      (node (ref "R12") (pin "2") (pinfunction "2_2") (pintype "passive"))
    )
    (net (code "60") (name "Net-(R13-Pad2)") (class "Default")
      (node (ref "R13") (pin "2") (pinfunction "2_2") (pintype "passive"))
      (node (ref "T1") (pin "G") (pinfunction "G_G") (pintype "passive"))
      (node (ref "T2") (pin "D") (pinfunction "D_D") (pintype "passive"))
    )
    (net (code "61") (name "Net-(R36-Pad2)") (class "Default")
      (node (ref "R36") (pin "2") (pinfunction "2_2") (pintype "passive"))
      (node (ref "R4") (pin "1") (pinfunction "1_1") (pintype "passive"))
    )
    (net (code "62") (name "Net-(U2-ADC{slash}TOUT)") (class "Default")
      (node (ref "R2") (pin "1") (pinfunction "1_1") (pintype "passive"))
      (node (ref "U2") (pin "2") (pinfunction "ADC/TOUT_2") (pintype "passive"))
    )
    (net (code "63") (name "Net-(U2-GPIO12)") (class "Default")
      (node (ref "R8") (pin "1") (pinfunction "1_1") (pintype "passive"))
      (node (ref "U2") (pin "6") (pinfunction "GPIO12_6") (pintype "passive"))
    )
    (net (code "64") (name "Net-(U4-GND)") (class "Default")
      (node (ref "R35") (pin "1") (pinfunction "1_1") (pintype "passive"))
      (node (ref "U4") (pin "8") (pinfunction "GND_8") (pintype "passive"))
    )
    (net (code "65") (name "unconnected-(D1-DOUT-Pad2)") (class "Default")
      (node (ref "D1") (pin "2") (pinfunction "DOUT_2") (pintype "passive"))
    )
    (net (code "66") (name "unconnected-(IC1-~{Y}-Pad6)") (class "Default")
      (node (ref "IC1") (pin "6") (pinfunction "~{Y}_6") (pintype "passive"))
    )
    (net (code "67") (name "unconnected-(U2-GPIO13-Pad7)") (class "Default")
      (node (ref "U2") (pin "7") (pinfunction "GPIO13_7") (pintype "passive"))
    )
    (net (code "68") (name "unconnected-(U2-GPIO16-Pad4)") (class "Default")
      (node (ref "U2") (pin "4") (pinfunction "GPIO16_4") (pintype "passive"))
    )
    (net (code "69") (name "unconnected-(U2-REST-Pad1)") (class "Default")
      (node (ref "U2") (pin "1") (pinfunction "REST_1") (pintype "passive+no_connect"))
    )
    (net (code "70") (name "unconnected-(U3-QA-Pad9)") (class "Default")
      (node (ref "U3") (pin "9") (pinfunction "QA_9") (pintype "output"))
    )
    (net (code "71") (name "unconnected-(U3-QB-Pad7)") (class "Default")
      (node (ref "U3") (pin "7") (pinfunction "QB_7") (pintype "output"))
    )
    (net (code "72") (name "unconnected-(U3-QC-Pad6)") (class "Default")
      (node (ref "U3") (pin "6") (pinfunction "QC_6") (pintype "output"))
    )
    (net (code "73") (name "unconnected-(U3-QD-Pad5)") (class "Default")
      (node (ref "U3") (pin "5") (pinfunction "QD_5") (pintype "output"))
    )
    (net (code "74") (name "unconnected-(U3-QE-Pad3)") (class "Default")
      (node (ref "U3") (pin "3") (pinfunction "QE_3") (pintype "output"))
    )
    (net (code "75") (name "unconnected-(U3-QF-Pad2)") (class "Default")
      (node (ref "U3") (pin "2") (pinfunction "QF_2") (pintype "output"))
    )
    (net (code "76") (name "unconnected-(U3-QG-Pad4)") (class "Default")
      (node (ref "U3") (pin "4") (pinfunction "QG_4") (pintype "output"))
    )
    (net (code "77") (name "unconnected-(U3-QI-Pad12)") (class "Default")
      (node (ref "U3") (pin "12") (pinfunction "QI_12") (pintype "output"))
    )
    (net (code "78") (name "unconnected-(U3-QJ-Pad14)") (class "Default")
      (node (ref "U3") (pin "14") (pinfunction "QJ_14") (pintype "output"))
    )
    (net (code "79") (name "unconnected-(U3-QK-Pad15)") (class "Default")
      (node (ref "U3") (pin "15") (pinfunction "QK_15") (pintype "output"))
    )
    (net (code "80") (name "unconnected-(U3-QL-Pad1)") (class "Default")
      (node (ref "U3") (pin "1") (pinfunction "QL_1") (pintype "output"))
    )
    (net (code "81") (name "unconnected-(U4-INT-Pad13)") (class "Default")
      (node (ref "U4") (pin "13") (pinfunction "INT_13") (pintype "passive"))
    )
    (net (code "82") (name "unconnected-(U4-Q3-Pad7)") (class "Default")
      (node (ref "U4") (pin "7") (pinfunction "Q3_7") (pintype "passive"))
    )
    (net (code "83") (name "unconnected-(U4-Q6-Pad11)") (class "Default")
      (node (ref "U4") (pin "11") (pinfunction "Q6_11") (pintype "passive"))
    )
    (net (code "84") (name "unconnected-(U4-Q7-Pad12)") (class "Default")
      (node (ref "U4") (pin "12") (pinfunction "Q7_12") (pintype "passive"))
    )
    (net (code "85") (name "unconnected-(U5-INT-Pad13)") (class "Default")
      (node (ref "U5") (pin "13") (pinfunction "INT_13") (pintype "passive"))
    )
  )
)
